# Sheet1.net
KiCad netlist of a schematic drawn in Altium Designer
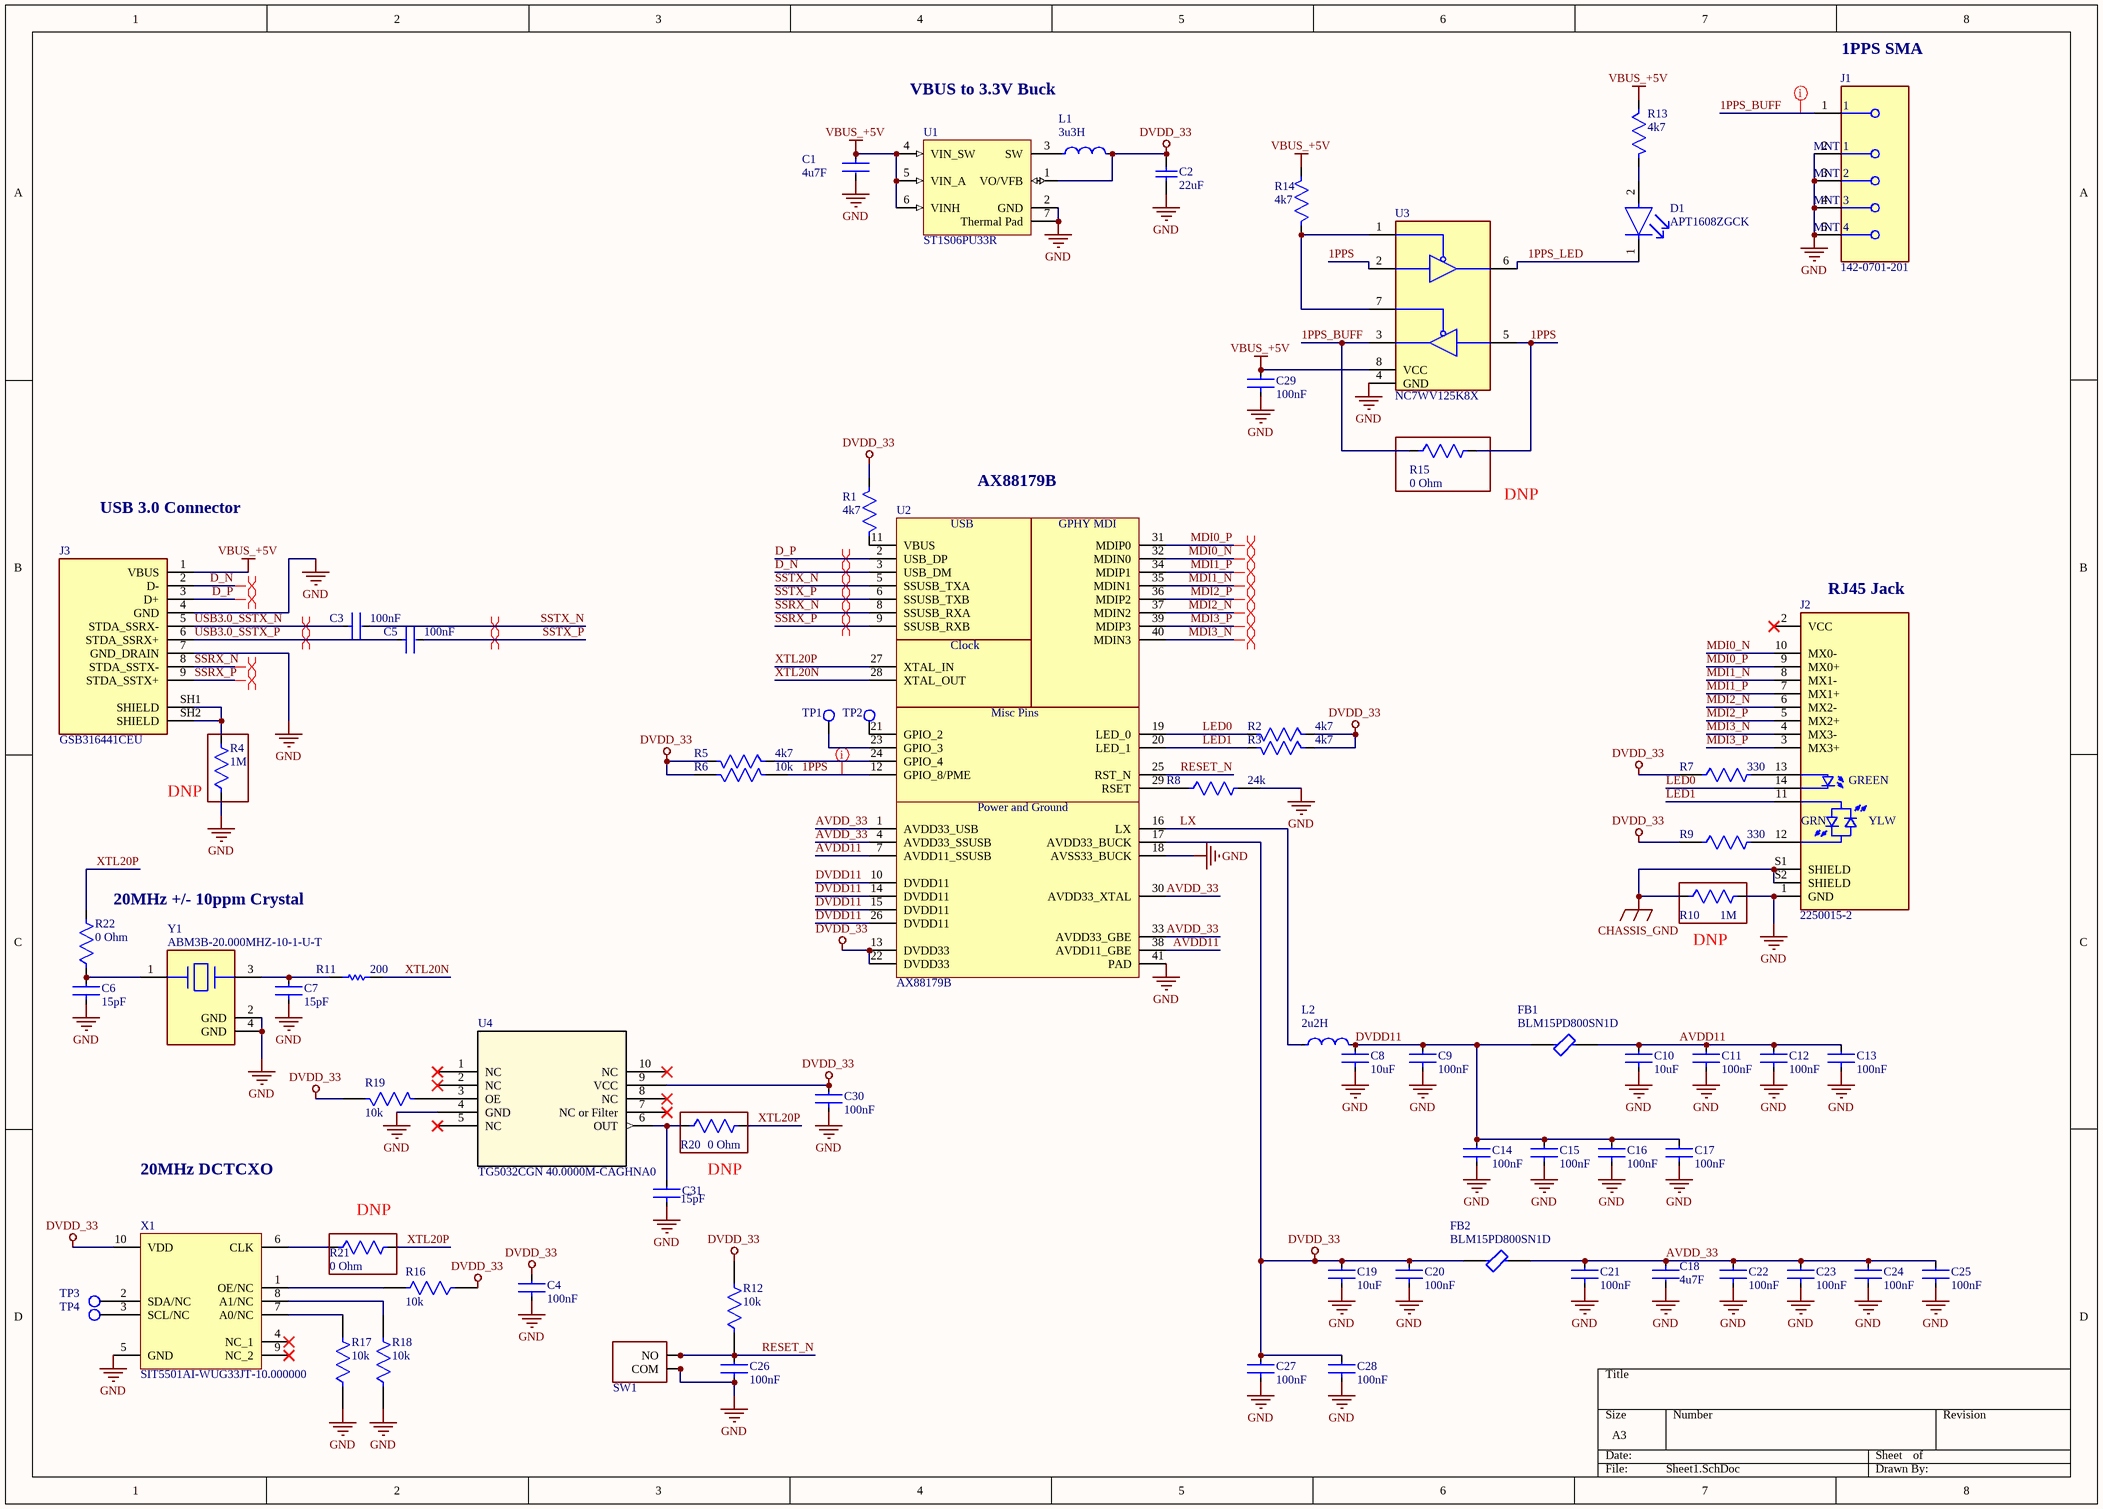
[diagram p0: Sheet1.SchDoc]

(export (version "E")
  (design (tool "Eeschema 10.0.6"))
  (components
    (comp (ref "C1")
      (value "4u7F")
      (footprint "FP-0402-L_1_0_0_15-W_0_5-IPC_C")
      (description "Ceramic Capacitor General Use 4.7uF ±20% 10V X5R 0402")
      (fields (field (name "TOLERANCE") "20%") (field (name "MANUFACTURER") "Taiyo Yuden"))
      (libsource (lib "Altium Content Vault") (part "236180d848d6139a670b325ea6854c9"))
    )
    (comp (ref "C2")
      (value "22uF")
      (footprint "CAPC1608X100X20ML10")
      (description "Chip Capacitor, 22 uF, +/- 20%, 10 V, -55 to 85 degC, 0603 (1608 Metric), RoHS, Tape and Reel")
      (fields (field (name "MANUFACTURER") "TDK") (field (name "TOLERANCE") "±20%"))
      (libsource (lib "Altium Content Vault") (part "CAP-NP-2"))
    )
    (comp (ref "C3")
      (value "100nF")
      (footprint "FP-CL251-IPC_C")
      (description "Cap Ceramic 100nF 10V X7R ±10% SMD 0402 +125°C Paper T/R")
      (fields (field (name "TOLERANCE") "10%") (field (name "MANUFACTURER") "KEMET"))
      (libsource (lib "Altium Content Vault") (part "b4654b650e69147ec39a6b967a45e02"))
    )
    (comp (ref "C4")
      (value "100nF")
      (footprint "FP-CL251-IPC_C")
      (description "Cap Ceramic 100nF 10V X7R ±10% SMD 0402 +125°C Paper T/R")
      (fields (field (name "TOLERANCE") "10%") (field (name "MANUFACTURER") "KEMET"))
      (libsource (lib "Altium Content Vault") (part "b4654b650e69147ec39a6b967a45e02"))
    )
    (comp (ref "C5")
      (value "100nF")
      (footprint "FP-CL251-IPC_C")
      (description "Cap Ceramic 100nF 10V X7R ±10% SMD 0402 +125°C Paper T/R")
      (fields (field (name "TOLERANCE") "10%") (field (name "MANUFACTURER") "KEMET"))
      (libsource (lib "Altium Content Vault") (part "b4654b650e69147ec39a6b967a45e02"))
    )
    (comp (ref "C6")
      (value "15pF")
      (footprint "FP-CBR04C-MFG")
      (description "CAP CER 15PF 100V C0G/NP0 0402")
      (fields
        (field (name "MANUFACTURER") "KEMET")
        (field (name "OCTOPART") "https://octopart.com/cbr04c150f1gac-kemet-30609229")
      )
      (libsource (lib "Altium Content Vault") (part "236180d848d6139a670b325ea6854c9"))
    )
    (comp (ref "C7")
      (value "15pF")
      (footprint "FP-CBR04C-MFG")
      (description "CAP CER 15PF 100V C0G/NP0 0402")
      (fields
        (field (name "MANUFACTURER") "KEMET")
        (field (name "OCTOPART") "https://octopart.com/cbr04c150f1gac-kemet-30609229")
      )
      (libsource (lib "Altium Content Vault") (part "236180d848d6139a670b325ea6854c9"))
    )
    (comp (ref "C8")
      (value "10uF")
      (footprint "FP-CL05A106MP5NUNC-MFG")
      (description "CAP CER 10UF 10V X5R 0402")
      (fields
        (field (name "OCTOPART") "https://octopart.com/cl05a106mp5nunc-samsung-22457395")
        (field (name "TOLERANCE") "20%")
      )
      (libsource (lib "Altium Content Vault") (part "b4654b650e69147ec39a6b967a45e02"))
    )
    (comp (ref "C9")
      (value "100nF")
      (footprint "FP-CL251-IPC_C")
      (description "Cap Ceramic 100nF 10V X7R ±10% SMD 0402 +125°C Paper T/R")
      (fields (field (name "TOLERANCE") "10%") (field (name "MANUFACTURER") "KEMET"))
      (libsource (lib "Altium Content Vault") (part "b4654b650e69147ec39a6b967a45e02"))
    )
    (comp (ref "C10")
      (value "10uF")
      (footprint "FP-CL05A106MP5NUNC-MFG")
      (description "CAP CER 10UF 10V X5R 0402")
      (fields
        (field (name "OCTOPART") "https://octopart.com/cl05a106mp5nunc-samsung-22457395")
        (field (name "TOLERANCE") "20%")
      )
      (libsource (lib "Altium Content Vault") (part "b4654b650e69147ec39a6b967a45e02"))
    )
    (comp (ref "C11")
      (value "100nF")
      (footprint "FP-CL251-IPC_C")
      (description "Cap Ceramic 100nF 10V X7R ±10% SMD 0402 +125°C Paper T/R")
      (fields (field (name "TOLERANCE") "10%") (field (name "MANUFACTURER") "KEMET"))
      (libsource (lib "Altium Content Vault") (part "b4654b650e69147ec39a6b967a45e02"))
    )
    (comp (ref "C12")
      (value "100nF")
      (footprint "FP-CL251-IPC_C")
      (description "Cap Ceramic 100nF 10V X7R ±10% SMD 0402 +125°C Paper T/R")
      (fields (field (name "TOLERANCE") "10%") (field (name "MANUFACTURER") "KEMET"))
      (libsource (lib "Altium Content Vault") (part "b4654b650e69147ec39a6b967a45e02"))
    )
    (comp (ref "C13")
      (value "100nF")
      (footprint "FP-CL251-IPC_C")
      (description "Cap Ceramic 100nF 10V X7R ±10% SMD 0402 +125°C Paper T/R")
      (fields (field (name "TOLERANCE") "10%") (field (name "MANUFACTURER") "KEMET"))
      (libsource (lib "Altium Content Vault") (part "b4654b650e69147ec39a6b967a45e02"))
    )
    (comp (ref "C14")
      (value "100nF")
      (footprint "FP-CL251-IPC_C")
      (description "Cap Ceramic 100nF 10V X7R ±10% SMD 0402 +125°C Paper T/R")
      (fields (field (name "TOLERANCE") "10%") (field (name "MANUFACTURER") "KEMET"))
      (libsource (lib "Altium Content Vault") (part "b4654b650e69147ec39a6b967a45e02"))
    )
    (comp (ref "C15")
      (value "100nF")
      (footprint "FP-CL251-IPC_C")
      (description "Cap Ceramic 100nF 10V X7R ±10% SMD 0402 +125°C Paper T/R")
      (fields (field (name "TOLERANCE") "10%") (field (name "MANUFACTURER") "KEMET"))
      (libsource (lib "Altium Content Vault") (part "b4654b650e69147ec39a6b967a45e02"))
    )
    (comp (ref "C16")
      (value "100nF")
      (footprint "FP-CL251-IPC_C")
      (description "Cap Ceramic 100nF 10V X7R ±10% SMD 0402 +125°C Paper T/R")
      (fields (field (name "TOLERANCE") "10%") (field (name "MANUFACTURER") "KEMET"))
      (libsource (lib "Altium Content Vault") (part "b4654b650e69147ec39a6b967a45e02"))
    )
    (comp (ref "C17")
      (value "100nF")
      (footprint "FP-CL251-IPC_C")
      (description "Cap Ceramic 100nF 10V X7R ±10% SMD 0402 +125°C Paper T/R")
      (fields (field (name "TOLERANCE") "10%") (field (name "MANUFACTURER") "KEMET"))
      (libsource (lib "Altium Content Vault") (part "b4654b650e69147ec39a6b967a45e02"))
    )
    (comp (ref "C18")
      (value "4u7F")
      (footprint "FP-0402-L_1_0_0_15-W_0_5-IPC_C")
      (description "Ceramic Capacitor General Use 4.7uF ±20% 10V X5R 0402")
      (fields (field (name "TOLERANCE") "20%") (field (name "MANUFACTURER") "Taiyo Yuden"))
      (libsource (lib "Altium Content Vault") (part "236180d848d6139a670b325ea6854c9"))
    )
    (comp (ref "C19")
      (value "10uF")
      (footprint "FP-CL05A106MP5NUNC-MFG")
      (description "CAP CER 10UF 10V X5R 0402")
      (fields
        (field (name "OCTOPART") "https://octopart.com/cl05a106mp5nunc-samsung-22457395")
        (field (name "TOLERANCE") "20%")
      )
      (libsource (lib "Altium Content Vault") (part "b4654b650e69147ec39a6b967a45e02"))
    )
    (comp (ref "C20")
      (value "100nF")
      (footprint "FP-CL251-IPC_C")
      (description "Cap Ceramic 100nF 10V X7R ±10% SMD 0402 +125°C Paper T/R")
      (fields (field (name "TOLERANCE") "10%") (field (name "MANUFACTURER") "KEMET"))
      (libsource (lib "Altium Content Vault") (part "b4654b650e69147ec39a6b967a45e02"))
    )
    (comp (ref "C21")
      (value "100nF")
      (footprint "FP-CL251-IPC_C")
      (description "Cap Ceramic 100nF 10V X7R ±10% SMD 0402 +125°C Paper T/R")
      (fields (field (name "TOLERANCE") "10%") (field (name "MANUFACTURER") "KEMET"))
      (libsource (lib "Altium Content Vault") (part "b4654b650e69147ec39a6b967a45e02"))
    )
    (comp (ref "C22")
      (value "100nF")
      (footprint "FP-CL251-IPC_C")
      (description "Cap Ceramic 100nF 10V X7R ±10% SMD 0402 +125°C Paper T/R")
      (fields (field (name "TOLERANCE") "10%") (field (name "MANUFACTURER") "KEMET"))
      (libsource (lib "Altium Content Vault") (part "b4654b650e69147ec39a6b967a45e02"))
    )
    (comp (ref "C23")
      (value "100nF")
      (footprint "FP-CL251-IPC_C")
      (description "Cap Ceramic 100nF 10V X7R ±10% SMD 0402 +125°C Paper T/R")
      (fields (field (name "TOLERANCE") "10%") (field (name "MANUFACTURER") "KEMET"))
      (libsource (lib "Altium Content Vault") (part "b4654b650e69147ec39a6b967a45e02"))
    )
    (comp (ref "C24")
      (value "100nF")
      (footprint "FP-CL251-IPC_C")
      (description "Cap Ceramic 100nF 10V X7R ±10% SMD 0402 +125°C Paper T/R")
      (fields (field (name "TOLERANCE") "10%") (field (name "MANUFACTURER") "KEMET"))
      (libsource (lib "Altium Content Vault") (part "b4654b650e69147ec39a6b967a45e02"))
    )
    (comp (ref "C25")
      (value "100nF")
      (footprint "FP-CL251-IPC_C")
      (description "Cap Ceramic 100nF 10V X7R ±10% SMD 0402 +125°C Paper T/R")
      (fields (field (name "TOLERANCE") "10%") (field (name "MANUFACTURER") "KEMET"))
      (libsource (lib "Altium Content Vault") (part "b4654b650e69147ec39a6b967a45e02"))
    )
    (comp (ref "C26")
      (value "100nF")
      (footprint "FP-CL251-IPC_C")
      (description "Cap Ceramic 100nF 10V X7R ±10% SMD 0402 +125°C Paper T/R")
      (fields (field (name "TOLERANCE") "10%") (field (name "MANUFACTURER") "KEMET"))
      (libsource (lib "Altium Content Vault") (part "b4654b650e69147ec39a6b967a45e02"))
    )
    (comp (ref "C27")
      (value "100nF")
      (footprint "FP-CL251-IPC_C")
      (description "Cap Ceramic 100nF 10V X7R ±10% SMD 0402 +125°C Paper T/R")
      (fields (field (name "TOLERANCE") "10%") (field (name "MANUFACTURER") "KEMET"))
      (libsource (lib "Altium Content Vault") (part "b4654b650e69147ec39a6b967a45e02"))
    )
    (comp (ref "C28")
      (value "100nF")
      (footprint "FP-CL251-IPC_C")
      (description "Cap Ceramic 100nF 10V X7R ±10% SMD 0402 +125°C Paper T/R")
      (fields (field (name "TOLERANCE") "10%") (field (name "MANUFACTURER") "KEMET"))
      (libsource (lib "Altium Content Vault") (part "b4654b650e69147ec39a6b967a45e02"))
    )
    (comp (ref "C29")
      (value "100nF")
      (footprint "FP-CL251-IPC_C")
      (description "Cap Ceramic 100nF 10V X7R ±10% SMD 0402 +125°C Paper T/R")
      (fields (field (name "TOLERANCE") "10%") (field (name "MANUFACTURER") "KEMET"))
      (libsource (lib "Altium Content Vault") (part "b4654b650e69147ec39a6b967a45e02"))
    )
    (comp (ref "C30")
      (value "100nF")
      (footprint "FP-CL251-IPC_C")
      (description "Cap Ceramic 100nF 10V X7R ±10% SMD 0402 +125°C Paper T/R")
      (fields (field (name "TOLERANCE") "10%") (field (name "MANUFACTURER") "KEMET"))
      (libsource (lib "Altium Content Vault") (part "b4654b650e69147ec39a6b967a45e02"))
    )
    (comp (ref "C31")
      (value "15pF")
      (footprint "FP-CBR04C-MFG")
      (description "CAP CER 15PF 100V C0G/NP0 0402")
      (fields
        (field (name "MANUFACTURER") "KEMET")
        (field (name "OCTOPART") "https://octopart.com/cbr04c150f1gac-kemet-30609229")
      )
      (libsource (lib "Altium Content Vault") (part "236180d848d6139a670b325ea6854c9"))
    )
    (comp (ref "D1")
      (value "APT1608ZGCK")
      (footprint "FP-APT1608ZGCK-MFG")
      (description "LED GREEN CLEAR CHIP SMD")
      (fields (field (name "MANUFACTURER") "Kingbright"))
      (libsource (lib "Altium Content Vault") (part "8706943c75ba83719d021d2fdc84c58"))
    )
    (comp (ref "FB1")
      (value "BLM15PD800SN1D")
      (footprint "FP-BLM15-0_05-MFG")
      (description "Chip Ferrite Bead, 0402, 80Ω @ 100MHz, 0.07Ω, 25%, 1.5A")
      (fields (field (name "TOLERANCE") "25%") (field (name "MANUFACTURER") "Murata"))
      (libsource (lib "Altium Content Vault") (part "5f30dd21d616792df468990f7003faa"))
    )
    (comp (ref "FB2")
      (value "BLM15PD800SN1D")
      (footprint "FP-BLM15-0_05-MFG")
      (description "Chip Ferrite Bead, 0402, 80Ω @ 100MHz, 0.07Ω, 25%, 1.5A")
      (fields (field (name "TOLERANCE") "25%") (field (name "MANUFACTURER") "Murata"))
      (libsource (lib "Altium Content Vault") (part "5f30dd21d616792df468990f7003faa"))
    )
    (comp (ref "J1")
      (value "142-0701-201")
      (footprint "FP-142-0701-201-MFG")
      (description "CONN SMA JACK STR 50 OHM PCB")
      (fields (field (name "MANUFACTURER") "Bel Cinch"))
      (libsource (lib "Altium Content Vault") (part "c65b8a639cdaef1819ea20b5466f8fa"))
    )
    (comp (ref "J2")
      (value "2250015-2")
      (footprint "CONN_2250015-2")
      (description "Modular Connectors / Ethernet Connectors 1X1 MAG45 GIG 7G140ET TAB W/ LEDS")
      (fields (field (name "MF") "TRP Connector") (field (name "MANUFACTURER") "Bel"))
      (libsource (lib "LotusSound") (part "CONN_2250015-2"))
    )
    (comp (ref "J3")
      (value "GSB316441CEU")
      (footprint "CONN_AMPHENOL_GSB316441CEU")
      (description "Conn USB 3.0 Type A PL 9 POS Solder RA SMD 9 Terminal 1 Port")
      (fields (field (name "MF") "Amphenol") (field (name "MANUFACTURER") "Amphenol Commercial"))
      (libsource (lib "LotusSound") (part "CONN_GSB316441CEU"))
    )
    (comp (ref "L1")
      (value "3u3H")
      (footprint "FP-LQM2HPN_G0-IPC_A")
      (description "Multilayer Type Inductor for Power Lines, 1008 (2520), 3.3μH, 20%, 0.125Ω, 1.2A")
      (fields (field (name "TOLERANCE") "20%") (field (name "MANUFACTURER") "Murata"))
      (libsource (lib "Altium Content Vault") (part "725321dda6339637d4d059423bc1c3c"))
    )
    (comp (ref "L2")
      (value "2u2H")
      (footprint "FP-MLZ2012-0_85-IPC_A")
      (description "Shielded Multilayer Inductor 2.2uH ±20% 800mA 156mΩ SMD 0805")
      (fields (field (name "TOLERANCE") "20%") (field (name "MANUFACTURER") "TDK"))
      (libsource (lib "Altium Content Vault") (part "725321dda6339637d4d059423bc1c3c"))
    )
    (comp (ref "R1")
      (value "4k7")
      (footprint "FP-RT0402-MFG")
      (description "RES SMD 4.7K OHM 0.1% 1/16W 0402")
      (fields
        (field (name "MANUFACTURER") "Yageo")
        (field (name "OCTOPART") "https://octopart.com/rt0402brd074k7l-yageo-1415343")
      )
      (libsource (lib "Altium Content Vault") (part "1029c3af85768c4190bb7ad29bc67b5"))
    )
    (comp (ref "R2")
      (value "4k7")
      (footprint "FP-RT0402-MFG")
      (description "RES SMD 4.7K OHM 0.1% 1/16W 0402")
      (fields
        (field (name "MANUFACTURER") "Yageo")
        (field (name "OCTOPART") "https://octopart.com/rt0402brd074k7l-yageo-1415343")
      )
      (libsource (lib "Altium Content Vault") (part "1029c3af85768c4190bb7ad29bc67b5"))
    )
    (comp (ref "R3")
      (value "4k7")
      (footprint "FP-RT0402-MFG")
      (description "RES SMD 4.7K OHM 0.1% 1/16W 0402")
      (fields
        (field (name "MANUFACTURER") "Yageo")
        (field (name "OCTOPART") "https://octopart.com/rt0402brd074k7l-yageo-1415343")
      )
      (libsource (lib "Altium Content Vault") (part "1029c3af85768c4190bb7ad29bc67b5"))
    )
    (comp (ref "R4")
      (value "1M")
      (footprint "FP-RMCF0402-MFG")
      (description "1MΩ ±5% 0.063W 0402 Thick Film Chip Resistor AEC-Q200 compliant")
      (fields (field (name "TOLERANCE") "5%") (field (name "MANUFACTURER") "Stackpole Electronics"))
      (libsource (lib "Altium Content Vault") (part "1029c3af85768c4190bb7ad29bc67b5"))
    )
    (comp (ref "R5")
      (value "4k7")
      (footprint "FP-RT0402-MFG")
      (description "RES SMD 4.7K OHM 0.1% 1/16W 0402")
      (fields
        (field (name "MANUFACTURER") "Yageo")
        (field (name "OCTOPART") "https://octopart.com/rt0402brd074k7l-yageo-1415343")
      )
      (libsource (lib "Altium Content Vault") (part "1029c3af85768c4190bb7ad29bc67b5"))
    )
    (comp (ref "R6")
      (value "10k")
      (footprint "FP-RMCF0402-IPC_C")
      (description "10kΩ ±1% 0.063W 0402 Thick Film Chip Resistor AEC-Q200 compliant")
      (fields (field (name "TOLERANCE") "1%") (field (name "MANUFACTURER") "Stackpole Electronics"))
      (libsource (lib "") (part "1029c3af85768c4190bb7ad29bc67b5_1"))
    )
    (comp (ref "R7")
      (value "330")
      (footprint "FP-RC1005-IPC_B")
      (description "Res Thick Film 0402 330Ω 1% 0.063W ±100ppm/°C Molded SMD T/R")
      (fields (field (name "TOLERANCE") "1%") (field (name "MANUFACTURER") "Samsung"))
      (libsource (lib "") (part "1029c3af85768c4190bb7ad29bc67b5_1"))
    )
    (comp (ref "R8")
      (value "24k")
      (footprint "FP-RT0402-MFG")
      (description "RES SMD 24K OHM 1% 1/16W 0402")
      (fields (field (name "MANUFACTURER PART NUMBER") "RT0402FRE0724KL") (field (name "TOLERANCE") "0.01"))
      (libsource (lib "") (part "1029c3af85768c4190bb7ad29bc67b5_1"))
    )
    (comp (ref "R9")
      (value "330")
      (footprint "FP-RC1005-IPC_B")
      (description "Res Thick Film 0402 330Ω 1% 0.063W ±100ppm/°C Molded SMD T/R")
      (fields (field (name "TOLERANCE") "1%") (field (name "MANUFACTURER") "Samsung"))
      (libsource (lib "") (part "1029c3af85768c4190bb7ad29bc67b5_1"))
    )
    (comp (ref "R10")
      (value "1M")
      (footprint "FP-RMCF0402-MFG")
      (description "1MΩ ±5% 0.063W 0402 Thick Film Chip Resistor AEC-Q200 compliant")
      (fields (field (name "TOLERANCE") "5%") (field (name "MANUFACTURER") "Stackpole Electronics"))
      (libsource (lib "Altium Content Vault") (part "1029c3af85768c4190bb7ad29bc67b5"))
    )
    (comp (ref "R11")
      (value "200")
      (footprint "RESC1005X40X25LL10T10")
      (fields
        (field (name "MANUFACTURER") "KOA Speer")
        (field (name "PART NUMBER") "RK73B1ETTP201J")
        (field (name "TOLERANCE") "5%")
      )
      (libsource (lib "Altium Content Vault") (part "RES"))
    )
    (comp (ref "R12")
      (value "10k")
      (footprint "FP-RMCF0402-IPC_C")
      (description "10kΩ ±1% 0.063W 0402 Thick Film Chip Resistor AEC-Q200 compliant")
      (fields (field (name "TOLERANCE") "1%") (field (name "MANUFACTURER") "Stackpole Electronics"))
      (libsource (lib "") (part "1029c3af85768c4190bb7ad29bc67b5_1"))
    )
    (comp (ref "R13")
      (value "4k7")
      (footprint "FP-RT0402-MFG")
      (description "RES SMD 4.7K OHM 0.1% 1/16W 0402")
      (fields
        (field (name "MANUFACTURER") "Yageo")
        (field (name "OCTOPART") "https://octopart.com/rt0402brd074k7l-yageo-1415343")
      )
      (libsource (lib "Altium Content Vault") (part "1029c3af85768c4190bb7ad29bc67b5"))
    )
    (comp (ref "R14")
      (value "4k7")
      (footprint "FP-RT0402-MFG")
      (description "RES SMD 4.7K OHM 0.1% 1/16W 0402")
      (fields
        (field (name "MANUFACTURER") "Yageo")
        (field (name "OCTOPART") "https://octopart.com/rt0402brd074k7l-yageo-1415343")
      )
      (libsource (lib "Altium Content Vault") (part "1029c3af85768c4190bb7ad29bc67b5"))
    )
    (comp (ref "R15")
      (value "0 Ohm")
      (footprint "FP-CR0402-IPC_B")
      (description "Thick Film Chip Resistors 0402 0Ω 0.0625W 5%")
      (fields (field (name "TOLERANCE") "5%") (field (name "MANUFACTURER") "Bourns"))
      (libsource (lib "Altium Content Vault") (part "1029c3af85768c4190bb7ad29bc67b5"))
    )
    (comp (ref "R16")
      (value "10k")
      (footprint "FP-RMCF0402-IPC_C")
      (description "10kΩ ±1% 0.063W 0402 Thick Film Chip Resistor AEC-Q200 compliant")
      (fields (field (name "TOLERANCE") "1%") (field (name "MANUFACTURER") "Stackpole Electronics"))
      (libsource (lib "") (part "1029c3af85768c4190bb7ad29bc67b5_1"))
    )
    (comp (ref "R17")
      (value "10k")
      (footprint "FP-RMCF0402-IPC_C")
      (description "10kΩ ±1% 0.063W 0402 Thick Film Chip Resistor AEC-Q200 compliant")
      (fields (field (name "TOLERANCE") "1%") (field (name "MANUFACTURER") "Stackpole Electronics"))
      (libsource (lib "") (part "1029c3af85768c4190bb7ad29bc67b5_1"))
    )
    (comp (ref "R18")
      (value "10k")
      (footprint "FP-RMCF0402-IPC_C")
      (description "10kΩ ±1% 0.063W 0402 Thick Film Chip Resistor AEC-Q200 compliant")
      (fields (field (name "TOLERANCE") "1%") (field (name "MANUFACTURER") "Stackpole Electronics"))
      (libsource (lib "") (part "1029c3af85768c4190bb7ad29bc67b5_1"))
    )
    (comp (ref "R19")
      (value "10k")
      (footprint "FP-RMCF0402-IPC_C")
      (description "10kΩ ±1% 0.063W 0402 Thick Film Chip Resistor AEC-Q200 compliant")
      (fields (field (name "TOLERANCE") "1%") (field (name "MANUFACTURER") "Stackpole Electronics"))
      (libsource (lib "") (part "1029c3af85768c4190bb7ad29bc67b5_1"))
    )
    (comp (ref "R20")
      (value "0 Ohm")
      (footprint "FP-CR0402-IPC_B")
      (description "Thick Film Chip Resistors 0402 0Ω 0.0625W 5%")
      (fields (field (name "TOLERANCE") "5%") (field (name "MANUFACTURER") "Bourns"))
      (libsource (lib "Altium Content Vault") (part "1029c3af85768c4190bb7ad29bc67b5"))
    )
    (comp (ref "R21")
      (value "0 Ohm")
      (footprint "FP-CR0402-IPC_B")
      (description "Thick Film Chip Resistors 0402 0Ω 0.0625W 5%")
      (fields (field (name "TOLERANCE") "5%") (field (name "MANUFACTURER") "Bourns"))
      (libsource (lib "Altium Content Vault") (part "1029c3af85768c4190bb7ad29bc67b5"))
    )
    (comp (ref "R22")
      (value "0 Ohm")
      (footprint "FP-CR0402-IPC_B")
      (description "Thick Film Chip Resistors 0402 0Ω 0.0625W 5%")
      (fields (field (name "TOLERANCE") "5%") (field (name "MANUFACTURER") "Bourns"))
      (libsource (lib "Altium Content Vault") (part "1029c3af85768c4190bb7ad29bc67b5"))
    )
    (comp (ref "SW1")
      (value "SW_PTS815_SJG_250_SMTR_LFS")
      (footprint "SW_PTS815SJG250SMTRLFS")
      (description "Switch Tactile N.O. SPST Button J-Bend 0.05A 12VDC 3.92N SMD T/R")
      (fields (field (name "MF") "C&K") (field (name "MP") "PTS815 SJG 250 SMTR LFS"))
      (libsource (lib "LotusSound") (part "SW_PTS815_SJG_250_SMTR_LFS"))
    )
    (comp (ref "TP1")
      (value "Test Point 1MM")
      (footprint "TP_PAD-1MM")
      (libsource (lib "LotusSound") (part "TP_PAD-1MM"))
    )
    (comp (ref "TP2")
      (value "Test Point 1MM")
      (footprint "TP_PAD-1MM")
      (libsource (lib "LotusSound") (part "TP_PAD-1MM"))
    )
    (comp (ref "TP3")
      (value "Test Point 1MM")
      (footprint "TP_PAD-1MM")
      (libsource (lib "LotusSound") (part "TP_PAD-1MM"))
    )
    (comp (ref "TP4")
      (value "Test Point 1MM")
      (footprint "TP_PAD-1MM")
      (libsource (lib "LotusSound") (part "TP_PAD-1MM"))
    )
    (comp (ref "U1")
      (value "ST1S06PU33R")
      (footprint "DFN6D_L")
      (fields (field (name "MANUFACTURER") "STMicroelectronics"))
      (libsource (lib "Altium Content Vault") (part "PM-DCDC-ST1S06-IL7"))
    )
    (comp (ref "U2")
      (value "AX88179B")
      (footprint "IC_AX88179B_QFN40_5X5")
      (libsource (lib "LotusSound") (part "IC_AX88179B"))
    )
    (comp (ref "U3")
      (value "NC7WV125K8X")
      (footprint "SamacSys:SOP50P310X90-8N")
      (description "Integrated Circuit")
      (fields (field (name "MOUSER PART NUMBER") "512-NC7WV125K8X"))
      (libsource (lib "SamacSys") (part "NC7WV125K8X"))
    )
    (comp (ref "U4")
      (value "TG5032CGN 40.0000M-CAGHNA0")
      (footprint "QFN10_TG5032CGN 40.0000M-CAGHNA0_EPS")
      (description "No Description Available")
      (fields (field (name "COPYRIGHT") "Copyright (C) 2024 Ultra Librarian. All rights reserved."))
      (libsource (lib "TG5032CGN40P0000M-CAGHNA0") (part "TG5032CGN 40.0000M-CAGHNA0"))
    )
    (comp (ref "X1")
      (value "SIT5501AI-WUG33JT-10.000000")
      (footprint "XTAL_SiT5501_70x50")
      (description "1 MHz  60 MHz, Elite X Stratum 3E Precision Oscillator")
      (libsource (lib "LotusSound") (part "XTAL_SIT5501AI-WUG33JT-10.000000"))
    )
    (comp (ref "Y1")
      (value "ABM3B-20.000MHZ-10-1-U-T")
      (footprint "FP-ABM3B-MFG")
      (description "Crystal 20MHz ±10ppm 10pF SMD-4 5mm x 3.2mm")
      (fields (field (name "TOLERANCE") "10ppm") (field (name "MANUFACTURER") "Abracon"))
      (libsource (lib "Altium Content Vault") (part "48e526d86b7f2615d98721063c72f49"))
    )
  )
  (nets
    (net (code "1") (name "/1PPS") (class "Default")
      (node (ref "R15") (pin "2") (pinfunction "2_2") (pintype "passive"))
      (node (ref "R6") (pin "2") (pinfunction "2_2") (pintype "passive"))
      (node (ref "U2") (pin "12") (pinfunction "GPIO_8/PME_12") (pintype "passive"))
      (node (ref "U3") (pin "2") (pintype "passive"))
      (node (ref "U3") (pin "5") (pintype "passive"))
    )
    (net (code "2") (name "/1PPS_BUFF") (class "Default")
      (node (ref "J1") (pin "1") (pinfunction "1_1") (pintype "passive"))
      (node (ref "R15") (pin "1") (pinfunction "1_1") (pintype "passive"))
      (node (ref "U3") (pin "3") (pintype "passive"))
    )
    (net (code "3") (name "/1PPS_LED") (class "Default")
      (node (ref "D1") (pin "1") (pinfunction "C_1") (pintype "passive"))
      (node (ref "U3") (pin "6") (pintype "passive"))
    )
    (net (code "4") (name "/AVDD11") (class "Default")
      (node (ref "C10") (pin "2") (pinfunction "2_2") (pintype "passive"))
      (node (ref "C11") (pin "2") (pinfunction "2_2") (pintype "passive"))
      (node (ref "C12") (pin "2") (pinfunction "2_2") (pintype "passive"))
      (node (ref "C13") (pin "2") (pinfunction "2_2") (pintype "passive"))
      (node (ref "FB1") (pin "2") (pinfunction "2_2") (pintype "passive"))
      (node (ref "U2") (pin "38") (pinfunction "AVDD11_GBE_38") (pintype "passive"))
      (node (ref "U2") (pin "7") (pinfunction "AVDD11_SSUSB_7") (pintype "passive"))
    )
    (net (code "5") (name "/AVDD_33") (class "Default")
      (node (ref "C18") (pin "2") (pinfunction "2_2") (pintype "passive"))
      (node (ref "C21") (pin "2") (pinfunction "2_2") (pintype "passive"))
      (node (ref "C22") (pin "2") (pinfunction "2_2") (pintype "passive"))
      (node (ref "C23") (pin "2") (pinfunction "2_2") (pintype "passive"))
      (node (ref "C24") (pin "2") (pinfunction "2_2") (pintype "passive"))
      (node (ref "C25") (pin "2") (pinfunction "2_2") (pintype "passive"))
      (node (ref "FB2") (pin "2") (pinfunction "2_2") (pintype "passive"))
      (node (ref "U2") (pin "1") (pinfunction "AVDD33_USB_1") (pintype "passive"))
      (node (ref "U2") (pin "30") (pinfunction "AVDD33_XTAL_30") (pintype "passive"))
      (node (ref "U2") (pin "33") (pinfunction "AVDD33_GBE_33") (pintype "passive"))
      (node (ref "U2") (pin "4") (pinfunction "AVDD33_SSUSB_4") (pintype "passive"))
    )
    (net (code "6") (name "/DVDD11") (class "Default")
      (node (ref "C14") (pin "2") (pinfunction "2_2") (pintype "passive"))
      (node (ref "C15") (pin "2") (pinfunction "2_2") (pintype "passive"))
      (node (ref "C16") (pin "2") (pinfunction "2_2") (pintype "passive"))
      (node (ref "C17") (pin "2") (pinfunction "2_2") (pintype "passive"))
      (node (ref "C8") (pin "2") (pinfunction "2_2") (pintype "passive"))
      (node (ref "C9") (pin "2") (pinfunction "2_2") (pintype "passive"))
      (node (ref "FB1") (pin "1") (pinfunction "1_1") (pintype "passive"))
      (node (ref "L2") (pin "2") (pinfunction "2_2") (pintype "passive"))
      (node (ref "U2") (pin "10") (pinfunction "DVDD11_10") (pintype "passive"))
      (node (ref "U2") (pin "14") (pinfunction "DVDD11_14") (pintype "passive"))
      (node (ref "U2") (pin "15") (pinfunction "DVDD11_15") (pintype "passive"))
      (node (ref "U2") (pin "26") (pinfunction "DVDD11_26") (pintype "passive"))
    )
    (net (code "7") (name "/D_N") (class "Default")
      (node (ref "J3") (pin "2") (pinfunction "D-_2") (pintype "passive"))
      (node (ref "U2") (pin "3") (pinfunction "USB_DM_3") (pintype "passive"))
    )
    (net (code "8") (name "/D_P") (class "Default")
      (node (ref "J3") (pin "3") (pinfunction "D+_3") (pintype "passive"))
      (node (ref "U2") (pin "2") (pinfunction "USB_DP_2") (pintype "passive"))
    )
    (net (code "9") (name "/LED0") (class "Default")
      (node (ref "J2") (pin "14") (pinfunction "GK_14") (pintype "passive"))
      (node (ref "R2") (pin "2") (pinfunction "2_2") (pintype "passive"))
      (node (ref "U2") (pin "19") (pinfunction "LED_0_19") (pintype "passive"))
    )
    (net (code "10") (name "/LED1") (class "Default")
      (node (ref "J2") (pin "11") (pinfunction "11_11") (pintype "passive"))
      (node (ref "R3") (pin "2") (pinfunction "2_2") (pintype "passive"))
      (node (ref "U2") (pin "20") (pinfunction "LED_1_20") (pintype "passive"))
    )
    (net (code "11") (name "/LX") (class "Default")
      (node (ref "L2") (pin "1") (pinfunction "1_1") (pintype "passive"))
      (node (ref "U2") (pin "16") (pinfunction "LX_16") (pintype "passive"))
    )
    (net (code "12") (name "/MDI0_N") (class "Default")
      (node (ref "J2") (pin "10") (pinfunction "MX0-_10") (pintype "passive"))
      (node (ref "U2") (pin "32") (pinfunction "MDIN0_32") (pintype "passive"))
    )
    (net (code "13") (name "/MDI0_P") (class "Default")
      (node (ref "J2") (pin "9") (pinfunction "MX0+_9") (pintype "passive"))
      (node (ref "U2") (pin "31") (pinfunction "MDIP0_31") (pintype "passive"))
    )
    (net (code "14") (name "/MDI1_N") (class "Default")
      (node (ref "J2") (pin "8") (pinfunction "MX1-_8") (pintype "passive"))
      (node (ref "U2") (pin "35") (pinfunction "MDIN1_35") (pintype "passive"))
    )
    (net (code "15") (name "/MDI1_P") (class "Default")
      (node (ref "J2") (pin "7") (pinfunction "MX1+_7") (pintype "passive"))
      (node (ref "U2") (pin "34") (pinfunction "MDIP1_34") (pintype "passive"))
    )
    (net (code "16") (name "/MDI2_N") (class "Default")
      (node (ref "J2") (pin "6") (pinfunction "MX2-_6") (pintype "passive"))
      (node (ref "U2") (pin "37") (pinfunction "MDIN2_37") (pintype "passive"))
    )
    (net (code "17") (name "/MDI2_P") (class "Default")
      (node (ref "J2") (pin "5") (pinfunction "MX2+_5") (pintype "passive"))
      (node (ref "U2") (pin "36") (pinfunction "MDIP2_36") (pintype "passive"))
    )
    (net (code "18") (name "/MDI3_N") (class "Default")
      (node (ref "J2") (pin "4") (pinfunction "MX3-_4") (pintype "passive"))
      (node (ref "U2") (pin "40") (pinfunction "MDIN3_40") (pintype "passive"))
    )
    (net (code "19") (name "/MDI3_P") (class "Default")
      (node (ref "J2") (pin "3") (pinfunction "MX3+_3") (pintype "passive"))
      (node (ref "U2") (pin "39") (pinfunction "MDIP3_39") (pintype "passive"))
    )
    (net (code "20") (name "/RESET_N") (class "Default")
      (node (ref "C26") (pin "2") (pinfunction "2_2") (pintype "passive"))
      (node (ref "R12") (pin "1") (pinfunction "1_1") (pintype "passive"))
      (node (ref "SW1") (pin "3") (pinfunction "NO_3") (pintype "passive"))
      (node (ref "SW1") (pin "4") (pinfunction "NO_4") (pintype "passive"))
      (node (ref "U2") (pin "25") (pinfunction "RST_N_25") (pintype "passive"))
    )
    (net (code "21") (name "/SSRX_N") (class "Default")
      (node (ref "J3") (pin "8") (pinfunction "STDA_SSTX-_8") (pintype "passive"))
      (node (ref "U2") (pin "8") (pinfunction "SSUSB_RXA_8") (pintype "passive"))
    )
    (net (code "22") (name "/SSRX_P") (class "Default")
      (node (ref "J3") (pin "9") (pinfunction "STDA_SSTX+_9") (pintype "passive"))
      (node (ref "U2") (pin "9") (pinfunction "SSUSB_RXB_9") (pintype "passive"))
    )
    (net (code "23") (name "/SSTX_N") (class "Default")
      (node (ref "C3") (pin "2") (pinfunction "2_2") (pintype "passive"))
      (node (ref "U2") (pin "5") (pinfunction "SSUSB_TXA_5") (pintype "passive"))
    )
    (net (code "24") (name "/SSTX_P") (class "Default")
      (node (ref "C5") (pin "2") (pinfunction "2_2") (pintype "passive"))
      (node (ref "U2") (pin "6") (pinfunction "SSUSB_TXB_6") (pintype "passive"))
    )
    (net (code "25") (name "/USB3.0_SSTX_N") (class "Default")
      (node (ref "C3") (pin "1") (pinfunction "1_1") (pintype "passive"))
      (node (ref "J3") (pin "5") (pinfunction "STDA_SSRX-_5") (pintype "passive"))
    )
    (net (code "26") (name "/USB3.0_SSTX_P") (class "Default")
      (node (ref "C5") (pin "1") (pinfunction "1_1") (pintype "passive"))
      (node (ref "J3") (pin "6") (pinfunction "STDA_SSRX+_6") (pintype "passive"))
    )
    (net (code "27") (name "/XTL20N") (class "Default")
      (node (ref "R11") (pin "2") (pinfunction "2_2") (pintype "passive"))
      (node (ref "U2") (pin "28") (pinfunction "XTAL_OUT_28") (pintype "passive"))
    )
    (net (code "28") (name "/XTL20P") (class "Default")
      (node (ref "R20") (pin "2") (pinfunction "2_2") (pintype "passive"))
      (node (ref "R21") (pin "2") (pinfunction "2_2") (pintype "passive"))
      (node (ref "R22") (pin "2") (pinfunction "2_2") (pintype "passive"))
      (node (ref "U2") (pin "27") (pinfunction "XTAL_IN_27") (pintype "passive"))
    )
    (net (code "29") (name "CHASSIS_GND") (class "Default")
      (node (ref "J2") (pin "S1") (pinfunction "SHIELD_S1") (pintype "passive"))
      (node (ref "J2") (pin "S2") (pinfunction "SHIELD_S2") (pintype "passive"))
      (node (ref "R10") (pin "1") (pinfunction "1_1") (pintype "passive"))
    )
    (net (code "30") (name "DVDD_33") (class "Default")
      (node (ref "C19") (pin "2") (pinfunction "2_2") (pintype "passive"))
      (node (ref "C2") (pin "2") (pinfunction "2_2") (pintype "passive"))
      (node (ref "C20") (pin "2") (pinfunction "2_2") (pintype "passive"))
      (node (ref "C27") (pin "2") (pinfunction "2_2") (pintype "passive"))
      (node (ref "C28") (pin "2") (pinfunction "2_2") (pintype "passive"))
      (node (ref "C30") (pin "2") (pinfunction "2_2") (pintype "passive"))
      (node (ref "C4") (pin "2") (pinfunction "2_2") (pintype "passive"))
      (node (ref "FB2") (pin "1") (pinfunction "1_1") (pintype "passive"))
      (node (ref "L1") (pin "2") (pinfunction "2_2") (pintype "passive"))
      (node (ref "R1") (pin "2") (pinfunction "2_2") (pintype "passive"))
      (node (ref "R12") (pin "2") (pinfunction "2_2") (pintype "passive"))
      (node (ref "R16") (pin "1") (pinfunction "1_1") (pintype "passive"))
      (node (ref "R19") (pin "1") (pinfunction "1_1") (pintype "passive"))
      (node (ref "R2") (pin "1") (pinfunction "1_1") (pintype "passive"))
      (node (ref "R3") (pin "1") (pinfunction "1_1") (pintype "passive"))
      (node (ref "R5") (pin "2") (pinfunction "2_2") (pintype "passive"))
      (node (ref "R6") (pin "1") (pinfunction "1_1") (pintype "passive"))
      (node (ref "R7") (pin "1") (pinfunction "1_1") (pintype "passive"))
      (node (ref "R9") (pin "1") (pinfunction "1_1") (pintype "passive"))
      (node (ref "U1") (pin "1") (pinfunction "VO/VFB_1") (pintype "bidirectional"))
      (node (ref "U2") (pin "13") (pinfunction "DVDD33_13") (pintype "passive"))
      (node (ref "U2") (pin "17") (pinfunction "AVDD33_BUCK_17") (pintype "passive"))
      (node (ref "U2") (pin "22") (pinfunction "DVDD33_22") (pintype "passive"))
      (node (ref "U4") (pin "9") (pinfunction "VCC_9") (pintype "power_in"))
      (node (ref "X1") (pin "10") (pinfunction "VDD_10") (pintype "passive"))
    )
    (net (code "31") (name "GND") (class "Default")
      (node (ref "C1") (pin "1") (pinfunction "1_1") (pintype "passive"))
      (node (ref "C10") (pin "1") (pinfunction "1_1") (pintype "passive"))
      (node (ref "C11") (pin "1") (pinfunction "1_1") (pintype "passive"))
      (node (ref "C12") (pin "1") (pinfunction "1_1") (pintype "passive"))
      (node (ref "C13") (pin "1") (pinfunction "1_1") (pintype "passive"))
      (node (ref "C14") (pin "1") (pinfunction "1_1") (pintype "passive"))
      (node (ref "C15") (pin "1") (pinfunction "1_1") (pintype "passive"))
      (node (ref "C16") (pin "1") (pinfunction "1_1") (pintype "passive"))
      (node (ref "C17") (pin "1") (pinfunction "1_1") (pintype "passive"))
      (node (ref "C18") (pin "1") (pinfunction "1_1") (pintype "passive"))
      (node (ref "C19") (pin "1") (pinfunction "1_1") (pintype "passive"))
      (node (ref "C2") (pin "1") (pinfunction "1_1") (pintype "passive"))
      (node (ref "C20") (pin "1") (pinfunction "1_1") (pintype "passive"))
      (node (ref "C21") (pin "1") (pinfunction "1_1") (pintype "passive"))
      (node (ref "C22") (pin "1") (pinfunction "1_1") (pintype "passive"))
      (node (ref "C23") (pin "1") (pinfunction "1_1") (pintype "passive"))
      (node (ref "C24") (pin "1") (pinfunction "1_1") (pintype "passive"))
      (node (ref "C25") (pin "1") (pinfunction "1_1") (pintype "passive"))
      (node (ref "C26") (pin "1") (pinfunction "1_1") (pintype "passive"))
      (node (ref "C27") (pin "1") (pinfunction "1_1") (pintype "passive"))
      (node (ref "C28") (pin "1") (pinfunction "1_1") (pintype "passive"))
      (node (ref "C29") (pin "1") (pinfunction "1_1") (pintype "passive"))
      (node (ref "C30") (pin "1") (pinfunction "1_1") (pintype "passive"))
      (node (ref "C31") (pin "2") (pinfunction "2_2") (pintype "passive"))
      (node (ref "C4") (pin "1") (pinfunction "1_1") (pintype "passive"))
      (node (ref "C6") (pin "2") (pinfunction "2_2") (pintype "passive"))
      (node (ref "C7") (pin "2") (pinfunction "2_2") (pintype "passive"))
      (node (ref "C8") (pin "1") (pinfunction "1_1") (pintype "passive"))
      (node (ref "C9") (pin "1") (pinfunction "1_1") (pintype "passive"))
      (node (ref "J1") (pin "2") (pinfunction "MNT_1_2") (pintype "passive"))
      (node (ref "J1") (pin "3") (pinfunction "MNT_2_3") (pintype "passive"))
      (node (ref "J1") (pin "4") (pinfunction "MNT_3_4") (pintype "passive"))
      (node (ref "J1") (pin "5") (pinfunction "MNT_4_5") (pintype "passive"))
      (node (ref "J2") (pin "1") (pinfunction "GND_1") (pintype "power_in"))
      (node (ref "J3") (pin "4") (pinfunction "GND_4") (pintype "power_in"))
      (node (ref "J3") (pin "7") (pinfunction "GND_DRAIN_7") (pintype "power_in"))
      (node (ref "R10") (pin "2") (pinfunction "2_2") (pintype "passive"))
      (node (ref "R17") (pin "1") (pinfunction "1_1") (pintype "passive"))
      (node (ref "R18") (pin "1") (pinfunction "1_1") (pintype "passive"))
      (node (ref "R4") (pin "1") (pinfunction "1_1") (pintype "passive"))
      (node (ref "R8") (pin "2") (pinfunction "2_2") (pintype "passive"))
      (node (ref "SW1") (pin "1") (pinfunction "COM_1") (pintype "passive"))
      (node (ref "SW1") (pin "2") (pinfunction "COM_2") (pintype "passive"))
      (node (ref "U1") (pin "2") (pinfunction "GND_2") (pintype "power_in"))
      (node (ref "U1") (pin "7") (pinfunction "Thermal_Pad_7") (pintype "power_in"))
      (node (ref "U2") (pin "18") (pinfunction "AVSS33_BUCK_18") (pintype "passive"))
      (node (ref "U2") (pin "41") (pinfunction "PAD_41") (pintype "passive"))
      (node (ref "U3") (pin "4") (pinfunction "GND_4") (pintype "passive"))
      (node (ref "U4") (pin "4") (pinfunction "GND_4") (pintype "power_in"))
      (node (ref "X1") (pin "5") (pinfunction "GND_5") (pintype "passive"))
      (node (ref "Y1") (pin "2") (pinfunction "GND_2") (pintype "power_in"))
      (node (ref "Y1") (pin "4") (pinfunction "GND_4") (pintype "power_in"))
    )
    (net (code "32") (name "Net-(C6-Pad1)") (class "Default")
      (node (ref "C6") (pin "1") (pinfunction "1_1") (pintype "passive"))
      (node (ref "R22") (pin "1") (pinfunction "1_1") (pintype "passive"))
      (node (ref "Y1") (pin "1") (pinfunction "1_1") (pintype "passive"))
    )
    (net (code "33") (name "Net-(C7-Pad1)") (class "Default")
      (node (ref "C7") (pin "1") (pinfunction "1_1") (pintype "passive"))
      (node (ref "R11") (pin "1") (pinfunction "1_1") (pintype "passive"))
      (node (ref "Y1") (pin "3") (pinfunction "3_3") (pintype "passive"))
    )
    (net (code "34") (name "Net-(D1-A)") (class "Default")
      (node (ref "D1") (pin "2") (pinfunction "A_2") (pintype "passive"))
      (node (ref "R13") (pin "2") (pinfunction "2_2") (pintype "passive"))
    )
    (net (code "35") (name "Net-(J2-GA)") (class "Default")
      (node (ref "J2") (pin "13") (pinfunction "GA_13") (pintype "passive"))
      (node (ref "R7") (pin "2") (pinfunction "2_2") (pintype "passive"))
    )
    (net (code "36") (name "Net-(J2-Pad12)") (class "Default")
      (node (ref "J2") (pin "12") (pinfunction "12_12") (pintype "passive"))
      (node (ref "R9") (pin "2") (pinfunction "2_2") (pintype "passive"))
    )
    (net (code "37") (name "Net-(J3-SHIELD-PadSH1)") (class "Default")
      (node (ref "J3") (pin "SH1") (pinfunction "SHIELD_SH1") (pintype "passive"))
      (node (ref "J3") (pin "SH2") (pinfunction "SHIELD_SH2") (pintype "passive"))
      (node (ref "R4") (pin "2") (pinfunction "2_2") (pintype "passive"))
    )
    (net (code "38") (name "Net-(R14-Pad1)") (class "Default")
      (node (ref "R14") (pin "1") (pinfunction "1_1") (pintype "passive"))
      (node (ref "U3") (pin "1") (pintype "passive"))
      (node (ref "U3") (pin "7") (pintype "passive"))
    )
    (net (code "39") (name "Net-(U1-SW)") (class "Default")
      (node (ref "L1") (pin "1") (pinfunction "1_1") (pintype "passive"))
      (node (ref "U1") (pin "3") (pinfunction "SW_3") (pintype "passive"))
    )
    (net (code "40") (name "Net-(U2-GPIO_2)") (class "Default")
      (node (ref "TP2") (pin "1") (pinfunction "1_1") (pintype "passive"))
      (node (ref "U2") (pin "21") (pinfunction "GPIO_2_21") (pintype "passive"))
    )
    (net (code "41") (name "Net-(U2-GPIO_3)") (class "Default")
      (node (ref "TP1") (pin "1") (pinfunction "1_1") (pintype "passive"))
      (node (ref "U2") (pin "23") (pinfunction "GPIO_3_23") (pintype "passive"))
    )
    (net (code "42") (name "Net-(U2-GPIO_4)") (class "Default")
      (node (ref "R5") (pin "1") (pinfunction "1_1") (pintype "passive"))
      (node (ref "U2") (pin "24") (pinfunction "GPIO_4_24") (pintype "passive"))
    )
    (net (code "43") (name "Net-(U2-RSET)") (class "Default")
      (node (ref "R8") (pin "1") (pinfunction "1_1") (pintype "passive"))
      (node (ref "U2") (pin "29") (pinfunction "RSET_29") (pintype "passive"))
    )
    (net (code "44") (name "Net-(U2-VBUS)") (class "Default")
      (node (ref "R1") (pin "1") (pinfunction "1_1") (pintype "passive"))
      (node (ref "U2") (pin "11") (pinfunction "VBUS_11") (pintype "passive"))
    )
    (net (code "45") (name "Net-(U4-OE)") (class "Default")
      (node (ref "R19") (pin "2") (pinfunction "2_2") (pintype "passive"))
      (node (ref "U4") (pin "3") (pinfunction "OE_3") (pintype "passive"))
    )
    (net (code "46") (name "Net-(U4-OUT)") (class "Default")
      (node (ref "C31") (pin "1") (pinfunction "1_1") (pintype "passive"))
      (node (ref "R20") (pin "1") (pinfunction "1_1") (pintype "passive"))
      (node (ref "U4") (pin "6") (pinfunction "OUT_6") (pintype "output"))
    )
    (net (code "47") (name "Net-(X1-A0{slash}NC)") (class "Default")
      (node (ref "R17") (pin "2") (pinfunction "2_2") (pintype "passive"))
      (node (ref "X1") (pin "7") (pinfunction "A0/NC_7") (pintype "passive"))
    )
    (net (code "48") (name "Net-(X1-A1{slash}NC)") (class "Default")
      (node (ref "R18") (pin "2") (pinfunction "2_2") (pintype "passive"))
      (node (ref "X1") (pin "8") (pinfunction "A1/NC_8") (pintype "passive"))
    )
    (net (code "49") (name "Net-(X1-CLK)") (class "Default")
      (node (ref "R21") (pin "1") (pinfunction "1_1") (pintype "passive"))
      (node (ref "X1") (pin "6") (pinfunction "CLK_6") (pintype "passive"))
    )
    (net (code "50") (name "Net-(X1-OE{slash}NC)") (class "Default")
      (node (ref "R16") (pin "2") (pinfunction "2_2") (pintype "passive"))
      (node (ref "X1") (pin "1") (pinfunction "OE/NC_1") (pintype "passive"))
    )
    (net (code "51") (name "Net-(X1-SCL{slash}NC)") (class "Default")
      (node (ref "TP4") (pin "1") (pinfunction "1_1") (pintype "passive"))
      (node (ref "X1") (pin "3") (pinfunction "SCL/NC_3") (pintype "passive"))
    )
    (net (code "52") (name "Net-(X1-SDA{slash}NC)") (class "Default")
      (node (ref "TP3") (pin "1") (pinfunction "1_1") (pintype "passive"))
      (node (ref "X1") (pin "2") (pinfunction "SDA/NC_2") (pintype "passive"))
    )
    (net (code "53") (name "VBUS_+5V") (class "Default")
      (node (ref "C1") (pin "2") (pinfunction "2_2") (pintype "passive"))
      (node (ref "C29") (pin "2") (pinfunction "2_2") (pintype "passive"))
      (node (ref "J3") (pin "1") (pinfunction "VBUS_1") (pintype "power_in"))
      (node (ref "R13") (pin "1") (pinfunction "1_1") (pintype "passive"))
      (node (ref "R14") (pin "2") (pinfunction "2_2") (pintype "passive"))
      (node (ref "U1") (pin "4") (pinfunction "VIN_SW_4") (pintype "input"))
      (node (ref "U1") (pin "5") (pinfunction "VIN_A_5") (pintype "input"))
      (node (ref "U1") (pin "6") (pinfunction "VINH_6") (pintype "input"))
      (node (ref "U3") (pin "8") (pinfunction "VCC_8") (pintype "passive"))
    )
    (net (code "54") (name "unconnected-(J2-VCC-Pad2)") (class "Default")
      (node (ref "J2") (pin "2") (pinfunction "VCC_2") (pintype "power_in+no_connect"))
    )
    (net (code "55") (name "unconnected-(U4-NC-Pad1)") (class "Default")
      (node (ref "U4") (pin "1") (pinfunction "NC_1") (pintype "passive+no_connect"))
    )
    (net (code "56") (name "unconnected-(U4-NC-Pad2)") (class "Default")
      (node (ref "U4") (pin "2") (pinfunction "NC_2") (pintype "passive+no_connect"))
    )
    (net (code "57") (name "unconnected-(U4-NC-Pad5)") (class "Default")
      (node (ref "U4") (pin "5") (pinfunction "NC_5") (pintype "passive+no_connect"))
    )
    (net (code "58") (name "unconnected-(U4-NC-Pad8)") (class "Default")
      (node (ref "U4") (pin "8") (pinfunction "NC_8") (pintype "passive+no_connect"))
    )
    (net (code "59") (name "unconnected-(U4-NC-Pad10)") (class "Default")
      (node (ref "U4") (pin "10") (pinfunction "NC_10") (pintype "passive+no_connect"))
    )
    (net (code "60") (name "unconnected-(U4-NC_or_Filter-Pad7)") (class "Default")
      (node (ref "U4") (pin "7") (pinfunction "NC_or_Filter_7") (pintype "passive+no_connect"))
    )
    (net (code "61") (name "unconnected-(X1-NC_1-Pad4)") (class "Default")
      (node (ref "X1") (pin "4") (pinfunction "NC_1_4") (pintype "passive+no_connect"))
    )
    (net (code "62") (name "unconnected-(X1-NC_2-Pad9)") (class "Default")
      (node (ref "X1") (pin "9") (pinfunction "NC_2_9") (pintype "passive+no_connect"))
    )
  )
)
